# MT9D111_interface.net
KiCad netlist of a schematic drawn in EAGLE
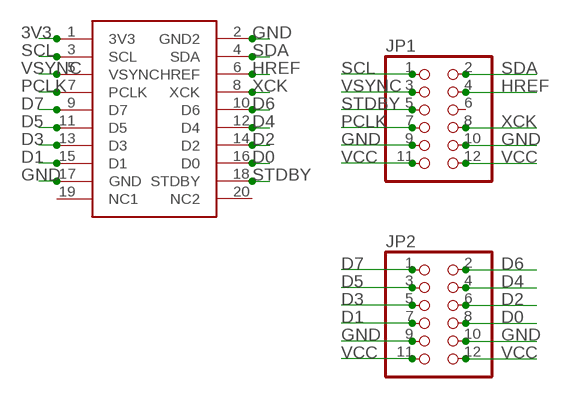
[diagram p0: schematic, sheet 1]

(export (version "E")
  (design (tool "Eeschema 10.0.6"))
  (components
    (comp (ref "JP1")
      (value "PINHD-2X6")
      (footprint "eagle-import:2X06")
      (libsource (lib "eagle-import") (part "PINHD-2X6"))
    )
    (comp (ref "JP2")
      (value "PINHD-2X6")
      (footprint "eagle-import:2X06")
      (libsource (lib "eagle-import") (part "PINHD-2X6"))
    )
    (comp (ref "U$1")
      (value "MT9D111")
      (footprint "eagle-import:10-2")
      (libsource (lib "eagle-import") (part "MT9D111"))
    )
  )
  (nets
    (net (code "1") (name "/3V3") (class "Default")
      (node (ref "U$1") (pin "1") (pinfunction "3V3_1") (pintype "bidirectional"))
    )
    (net (code "2") (name "/D0") (class "Default")
      (node (ref "JP2") (pin "8") (pinfunction "8_8") (pintype "passive"))
      (node (ref "U$1") (pin "16") (pinfunction "D0_16") (pintype "bidirectional"))
    )
    (net (code "3") (name "/D1") (class "Default")
      (node (ref "JP2") (pin "7") (pinfunction "7_7") (pintype "passive"))
      (node (ref "U$1") (pin "15") (pinfunction "D1_15") (pintype "bidirectional"))
    )
    (net (code "4") (name "/D2") (class "Default")
      (node (ref "JP2") (pin "6") (pinfunction "6_6") (pintype "passive"))
      (node (ref "U$1") (pin "14") (pinfunction "D2_14") (pintype "bidirectional"))
    )
    (net (code "5") (name "/D3") (class "Default")
      (node (ref "JP2") (pin "5") (pinfunction "5_5") (pintype "passive"))
      (node (ref "U$1") (pin "13") (pinfunction "D3_13") (pintype "bidirectional"))
    )
    (net (code "6") (name "/D4") (class "Default")
      (node (ref "JP2") (pin "4") (pinfunction "4_4") (pintype "passive"))
      (node (ref "U$1") (pin "12") (pinfunction "D4_12") (pintype "bidirectional"))
    )
    (net (code "7") (name "/D5") (class "Default")
      (node (ref "JP2") (pin "3") (pinfunction "3_3") (pintype "passive"))
      (node (ref "U$1") (pin "11") (pinfunction "D5_11") (pintype "bidirectional"))
    )
    (net (code "8") (name "/D6") (class "Default")
      (node (ref "JP2") (pin "2") (pinfunction "2_2") (pintype "passive"))
      (node (ref "U$1") (pin "10") (pinfunction "D6_10") (pintype "bidirectional"))
    )
    (net (code "9") (name "/D7") (class "Default")
      (node (ref "JP2") (pin "1") (pinfunction "1_1") (pintype "passive"))
      (node (ref "U$1") (pin "9") (pinfunction "D7_9") (pintype "bidirectional"))
    )
    (net (code "10") (name "/GND") (class "Default")
      (node (ref "JP1") (pin "10") (pinfunction "10_10") (pintype "passive"))
      (node (ref "JP1") (pin "9") (pinfunction "9_9") (pintype "passive"))
      (node (ref "JP2") (pin "10") (pinfunction "10_10") (pintype "passive"))
      (node (ref "JP2") (pin "9") (pinfunction "9_9") (pintype "passive"))
      (node (ref "U$1") (pin "17") (pinfunction "GND_17") (pintype "bidirectional"))
      (node (ref "U$1") (pin "2") (pinfunction "GND2_2") (pintype "bidirectional"))
    )
    (net (code "11") (name "/HREF") (class "Default")
      (node (ref "JP1") (pin "4") (pinfunction "4_4") (pintype "passive"))
      (node (ref "U$1") (pin "6") (pinfunction "HREF_6") (pintype "bidirectional"))
    )
    (net (code "12") (name "/PCLK") (class "Default")
      (node (ref "JP1") (pin "7") (pinfunction "7_7") (pintype "passive"))
      (node (ref "U$1") (pin "7") (pinfunction "PCLK_7") (pintype "bidirectional"))
    )
    (net (code "13") (name "/SCL") (class "Default")
      (node (ref "JP1") (pin "1") (pinfunction "1_1") (pintype "passive"))
      (node (ref "U$1") (pin "3") (pinfunction "SCL_3") (pintype "bidirectional"))
    )
    (net (code "14") (name "/SDA") (class "Default")
      (node (ref "JP1") (pin "2") (pinfunction "2_2") (pintype "passive"))
      (node (ref "U$1") (pin "4") (pinfunction "SDA_4") (pintype "bidirectional"))
    )
    (net (code "15") (name "/STDBY") (class "Default")
      (node (ref "JP1") (pin "5") (pinfunction "5_5") (pintype "passive"))
      (node (ref "U$1") (pin "18") (pinfunction "STDBY_18") (pintype "bidirectional"))
    )
    (net (code "16") (name "/VCC") (class "Default")
      (node (ref "JP1") (pin "11") (pinfunction "11_11") (pintype "passive"))
      (node (ref "JP1") (pin "12") (pinfunction "12_12") (pintype "passive"))
      (node (ref "JP2") (pin "11") (pinfunction "11_11") (pintype "passive"))
      (node (ref "JP2") (pin "12") (pinfunction "12_12") (pintype "passive"))
    )
    (net (code "17") (name "/VSYNC") (class "Default")
      (node (ref "JP1") (pin "3") (pinfunction "3_3") (pintype "passive"))
      (node (ref "U$1") (pin "5") (pinfunction "VSYNC_5") (pintype "bidirectional"))
    )
    (net (code "18") (name "/XCK") (class "Default")
      (node (ref "JP1") (pin "8") (pinfunction "8_8") (pintype "passive"))
      (node (ref "U$1") (pin "8") (pinfunction "XCK_8") (pintype "bidirectional"))
    )
    (net (code "19") (name "unconnected-(JP1-Pad6)") (class "Default")
      (node (ref "JP1") (pin "6") (pinfunction "6_6") (pintype "passive"))
    )
    (net (code "20") (name "unconnected-(U$1-NC1-Pad19)") (class "Default")
      (node (ref "U$1") (pin "19") (pinfunction "NC1_19") (pintype "bidirectional"))
    )
    (net (code "21") (name "unconnected-(U$1-NC2-Pad20)") (class "Default")
      (node (ref "U$1") (pin "20") (pinfunction "NC2_20") (pintype "bidirectional"))
    )
  )
)
